# WSN_Gateway_v3.net
KiCad netlist of a schematic drawn in EAGLE
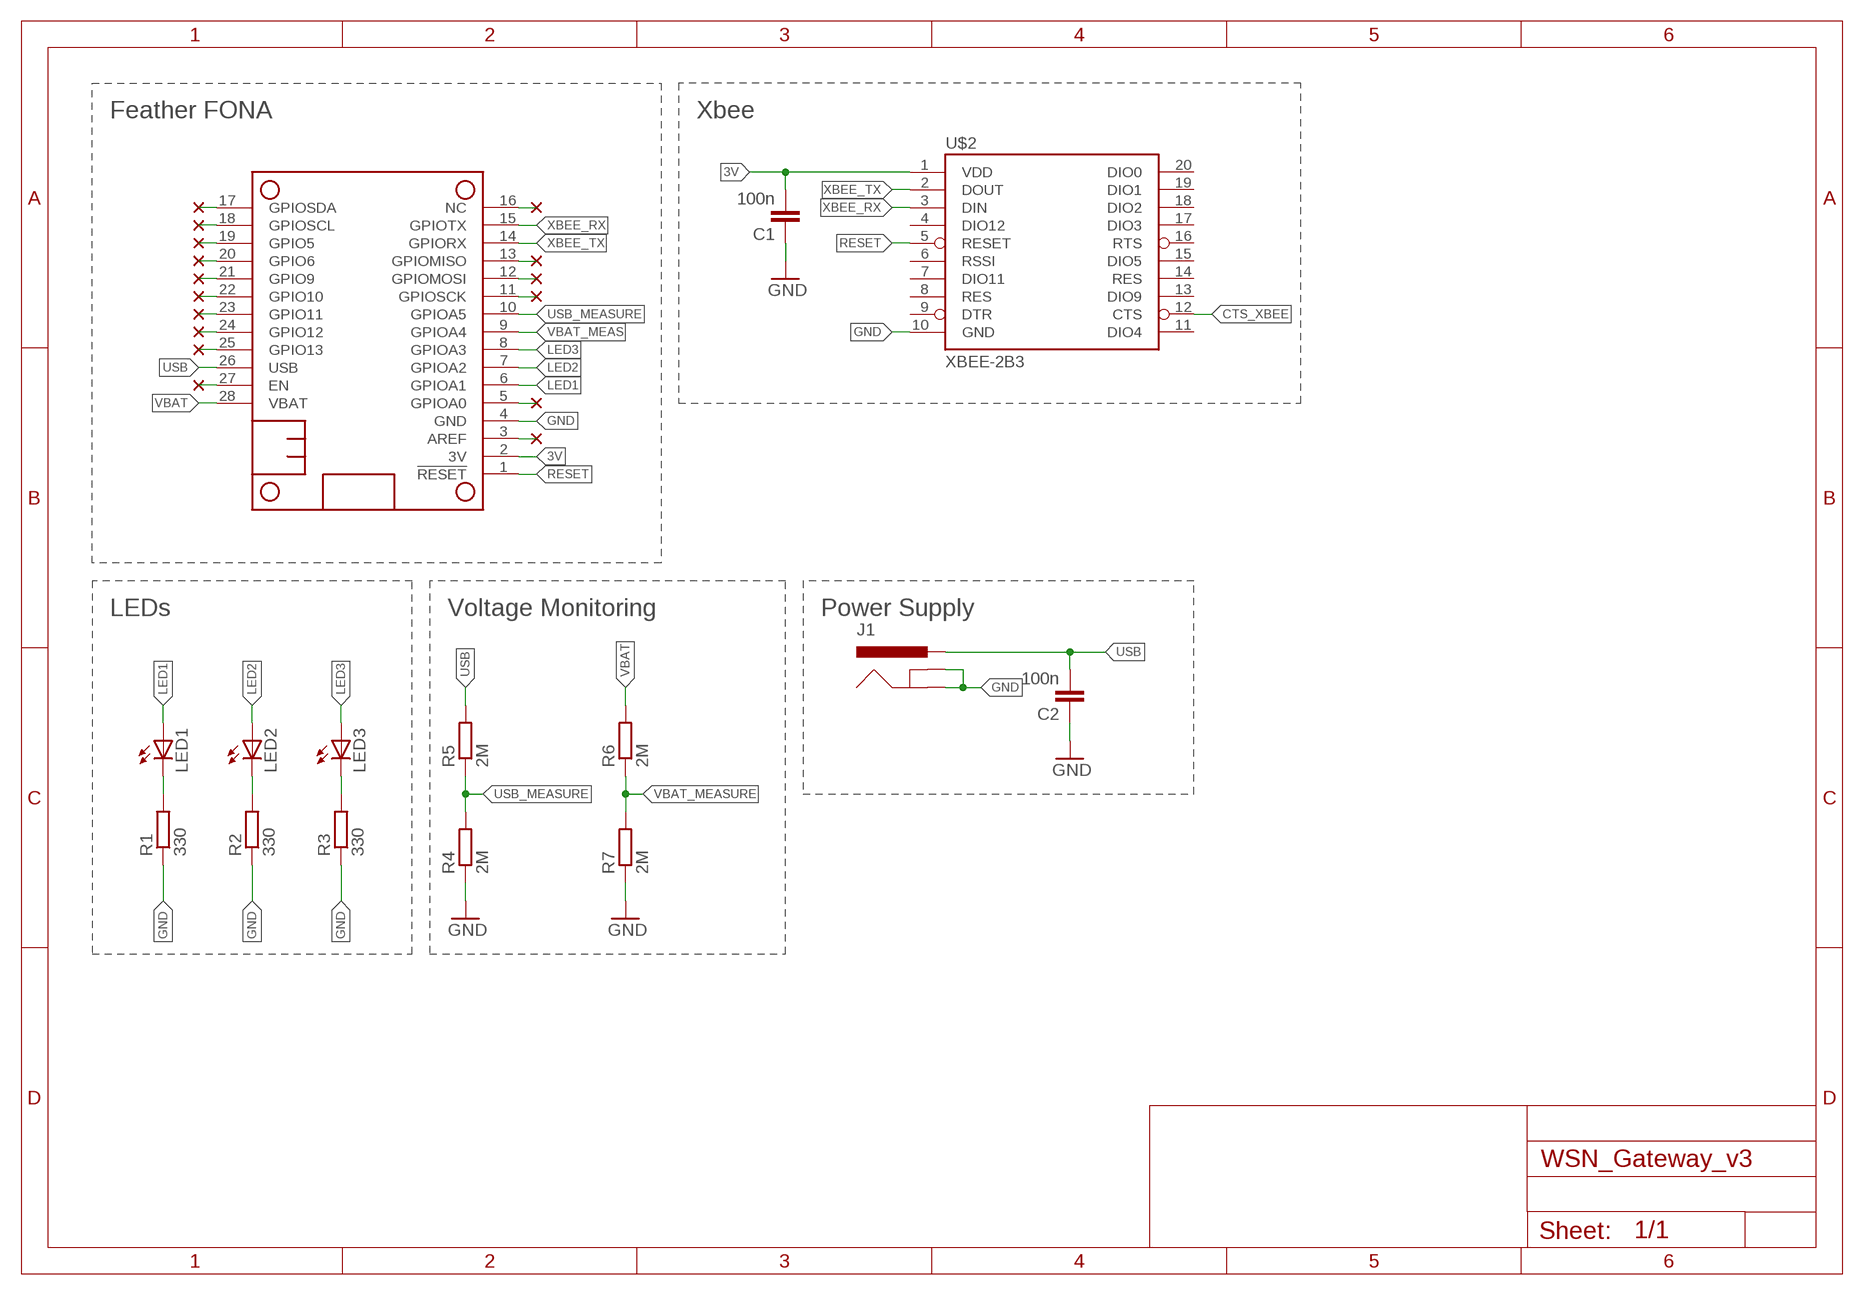
[diagram p0: schematic, sheet 1]

(export (version "E")
  (design (tool "Eeschema 10.0.6"))
  (components
    (comp (ref "C1")
      (value "100n")
      (footprint "eagle-import:C0805")
      (libsource (lib "eagle-import") (part "C"))
    )
    (comp (ref "C2")
      (value "100n")
      (footprint "eagle-import:C0805")
      (libsource (lib "eagle-import") (part "C"))
    )
    (comp (ref "J1")
      (value "5.5x2.1mm Barrel")
      (footprint "eagle-import:POWER_JACK_SMD")
      (libsource (lib "eagle-import") (part "POWER_JACKSMD"))
    )
    (comp (ref "LED1")
      (value "LEDCHIPLED_0805")
      (footprint "eagle-import:CHIPLED_0805")
      (libsource (lib "eagle-import") (part "LEDCHIPLED_0805"))
    )
    (comp (ref "LED2")
      (value "LEDCHIPLED_0805")
      (footprint "eagle-import:CHIPLED_0805")
      (libsource (lib "eagle-import") (part "LEDCHIPLED_0805"))
    )
    (comp (ref "LED3")
      (value "LEDCHIPLED_0805")
      (footprint "eagle-import:CHIPLED_0805")
      (libsource (lib "eagle-import") (part "LEDCHIPLED_0805"))
    )
    (comp (ref "MS1")
      (value "FEATHERWING_NODIM_NOHOLES")
      (footprint "eagle-import:FEATHERWING_DIM_2")
      (libsource (lib "eagle-import") (part "FEATHERWING_NODIM_NOHOLES"))
    )
    (comp (ref "R1")
      (value "330")
      (footprint "eagle-import:R0805")
      (libsource (lib "eagle-import") (part "R-EU_R0805"))
    )
    (comp (ref "R2")
      (value "330")
      (footprint "eagle-import:R0805")
      (libsource (lib "eagle-import") (part "R-EU_R0805"))
    )
    (comp (ref "R3")
      (value "330")
      (footprint "eagle-import:R0805")
      (libsource (lib "eagle-import") (part "R-EU_R0805"))
    )
    (comp (ref "R4")
      (value "2M")
      (footprint "eagle-import:R0805")
      (libsource (lib "eagle-import") (part "R-EU_R0805"))
    )
    (comp (ref "R5")
      (value "2M")
      (footprint "eagle-import:R0805")
      (libsource (lib "eagle-import") (part "R-EU_R0805"))
    )
    (comp (ref "R6")
      (value "2M")
      (footprint "eagle-import:R0805")
      (libsource (lib "eagle-import") (part "R-EU_R0805"))
    )
    (comp (ref "R7")
      (value "2M")
      (footprint "eagle-import:R0805")
      (libsource (lib "eagle-import") (part "R-EU_R0805"))
    )
    (comp (ref "U$2")
      (value "XBEE-2B3")
      (footprint "eagle-import:XBEE-SMD")
      (libsource (lib "eagle-import") (part "XBEE-2B3"))
    )
  )
  (nets
    (net (code "1") (name "3V") (class "Default")
      (node (ref "C1") (pin "2") (pinfunction "2_2") (pintype "passive"))
      (node (ref "MS1") (pin "2") (pinfunction "3V_2") (pintype "power_in"))
      (node (ref "U$2") (pin "1") (pinfunction "VDD_1") (pintype "power_in"))
    )
    (net (code "2") (name "CTS_XBEE") (class "Default")
      (node (ref "U$2") (pin "12") (pinfunction "CTS_12") (pintype "output"))
    )
    (net (code "3") (name "GND") (class "Default")
      (node (ref "C1") (pin "1") (pinfunction "1_1") (pintype "passive"))
      (node (ref "C2") (pin "1") (pinfunction "1_1") (pintype "passive"))
      (node (ref "J1") (pin "GND") (pinfunction "GNDBREAK_GND") (pintype "bidirectional"))
      (node (ref "J1") (pin "P$4") (pinfunction "GND_P$4") (pintype "bidirectional"))
      (node (ref "MS1") (pin "4") (pinfunction "GND_4") (pintype "power_in"))
      (node (ref "R1") (pin "1") (pinfunction "1_1") (pintype "passive"))
      (node (ref "R2") (pin "1") (pinfunction "1_1") (pintype "passive"))
      (node (ref "R3") (pin "1") (pinfunction "1_1") (pintype "passive"))
      (node (ref "R4") (pin "1") (pinfunction "1_1") (pintype "passive"))
      (node (ref "R7") (pin "1") (pinfunction "1_1") (pintype "passive"))
      (node (ref "U$2") (pin "10") (pinfunction "GND_10") (pintype "power_in"))
    )
    (net (code "4") (name "LED1") (class "Default")
      (node (ref "LED1") (pin "A") (pinfunction "A_A") (pintype "passive"))
      (node (ref "MS1") (pin "6") (pinfunction "GPIOA1_6") (pintype "bidirectional"))
    )
    (net (code "5") (name "LED2") (class "Default")
      (node (ref "LED2") (pin "A") (pinfunction "A_A") (pintype "passive"))
      (node (ref "MS1") (pin "7") (pinfunction "GPIOA2_7") (pintype "bidirectional"))
    )
    (net (code "6") (name "LED3") (class "Default")
      (node (ref "LED3") (pin "A") (pinfunction "A_A") (pintype "passive"))
      (node (ref "MS1") (pin "8") (pinfunction "GPIOA3_8") (pintype "bidirectional"))
    )
    (net (code "7") (name "Net-(LED1-PadC)") (class "Default")
      (node (ref "LED1") (pin "C") (pinfunction "C_C") (pintype "passive"))
      (node (ref "R1") (pin "2") (pinfunction "2_2") (pintype "passive"))
    )
    (net (code "8") (name "Net-(LED2-PadC)") (class "Default")
      (node (ref "LED2") (pin "C") (pinfunction "C_C") (pintype "passive"))
      (node (ref "R2") (pin "2") (pinfunction "2_2") (pintype "passive"))
    )
    (net (code "9") (name "Net-(LED3-PadC)") (class "Default")
      (node (ref "LED3") (pin "C") (pinfunction "C_C") (pintype "passive"))
      (node (ref "R3") (pin "2") (pinfunction "2_2") (pintype "passive"))
    )
    (net (code "10") (name "RESET") (class "Default")
      (node (ref "MS1") (pin "1") (pinfunction "~{RESET}_1") (pintype "input"))
      (node (ref "U$2") (pin "5") (pinfunction "RESET_5") (pintype "input"))
    )
    (net (code "11") (name "USB") (class "Default")
      (node (ref "C2") (pin "2") (pinfunction "2_2") (pintype "passive"))
      (node (ref "J1") (pin "VIN0") (pinfunction "PWR_VIN0") (pintype "bidirectional"))
      (node (ref "J1") (pin "VIN1") (pinfunction "PWR_VIN1") (pintype "bidirectional"))
      (node (ref "MS1") (pin "26") (pinfunction "USB_26") (pintype "power_in"))
      (node (ref "R5") (pin "2") (pinfunction "2_2") (pintype "passive"))
    )
    (net (code "12") (name "USB_MEASURE") (class "Default")
      (node (ref "MS1") (pin "10") (pinfunction "GPIOA5_10") (pintype "bidirectional"))
      (node (ref "R4") (pin "2") (pinfunction "2_2") (pintype "passive"))
      (node (ref "R5") (pin "1") (pinfunction "1_1") (pintype "passive"))
    )
    (net (code "13") (name "VBAT") (class "Default")
      (node (ref "MS1") (pin "28") (pinfunction "VBAT_28") (pintype "power_in"))
      (node (ref "R6") (pin "2") (pinfunction "2_2") (pintype "passive"))
    )
    (net (code "14") (name "VBAT_MEAS") (class "Default")
      (node (ref "MS1") (pin "9") (pinfunction "GPIOA4_9") (pintype "bidirectional"))
    )
    (net (code "15") (name "VBAT_MEASURE") (class "Default")
      (node (ref "R6") (pin "1") (pinfunction "1_1") (pintype "passive"))
      (node (ref "R7") (pin "2") (pinfunction "2_2") (pintype "passive"))
    )
    (net (code "16") (name "XBEE_RX") (class "Default")
      (node (ref "MS1") (pin "15") (pinfunction "GPIOTX_15") (pintype "bidirectional"))
      (node (ref "U$2") (pin "3") (pinfunction "DIN_3") (pintype "input"))
    )
    (net (code "17") (name "XBEE_TX") (class "Default")
      (node (ref "MS1") (pin "14") (pinfunction "GPIORX_14") (pintype "bidirectional"))
      (node (ref "U$2") (pin "2") (pinfunction "DOUT_2") (pintype "output"))
    )
    (net (code "18") (name "unconnected-(MS1-AREF-Pad3)") (class "Default")
      (node (ref "MS1") (pin "3") (pinfunction "AREF_3") (pintype "passive"))
    )
    (net (code "19") (name "unconnected-(MS1-EN-Pad27)") (class "Default")
      (node (ref "MS1") (pin "27") (pinfunction "EN_27") (pintype "passive"))
    )
    (net (code "20") (name "unconnected-(MS1-GPIO5-Pad19)") (class "Default")
      (node (ref "MS1") (pin "19") (pinfunction "GPIO5_19") (pintype "bidirectional"))
    )
    (net (code "21") (name "unconnected-(MS1-GPIO6-Pad20)") (class "Default")
      (node (ref "MS1") (pin "20") (pinfunction "GPIO6_20") (pintype "bidirectional"))
    )
    (net (code "22") (name "unconnected-(MS1-GPIO9-Pad21)") (class "Default")
      (node (ref "MS1") (pin "21") (pinfunction "GPIO9_21") (pintype "bidirectional"))
    )
    (net (code "23") (name "unconnected-(MS1-GPIO10-Pad22)") (class "Default")
      (node (ref "MS1") (pin "22") (pinfunction "GPIO10_22") (pintype "bidirectional"))
    )
    (net (code "24") (name "unconnected-(MS1-GPIO11-Pad23)") (class "Default")
      (node (ref "MS1") (pin "23") (pinfunction "GPIO11_23") (pintype "bidirectional"))
    )
    (net (code "25") (name "unconnected-(MS1-GPIO12-Pad24)") (class "Default")
      (node (ref "MS1") (pin "24") (pinfunction "GPIO12_24") (pintype "bidirectional"))
    )
    (net (code "26") (name "unconnected-(MS1-GPIO13-Pad25)") (class "Default")
      (node (ref "MS1") (pin "25") (pinfunction "GPIO13_25") (pintype "bidirectional"))
    )
    (net (code "27") (name "unconnected-(MS1-GPIOA0-Pad5)") (class "Default")
      (node (ref "MS1") (pin "5") (pinfunction "GPIOA0_5") (pintype "bidirectional"))
    )
    (net (code "28") (name "unconnected-(MS1-GPIOMISO-Pad13)") (class "Default")
      (node (ref "MS1") (pin "13") (pinfunction "GPIOMISO_13") (pintype "bidirectional"))
    )
    (net (code "29") (name "unconnected-(MS1-GPIOMOSI-Pad12)") (class "Default")
      (node (ref "MS1") (pin "12") (pinfunction "GPIOMOSI_12") (pintype "bidirectional"))
    )
    (net (code "30") (name "unconnected-(MS1-GPIOSCK-Pad11)") (class "Default")
      (node (ref "MS1") (pin "11") (pinfunction "GPIOSCK_11") (pintype "bidirectional"))
    )
    (net (code "31") (name "unconnected-(MS1-GPIOSCL-Pad18)") (class "Default")
      (node (ref "MS1") (pin "18") (pinfunction "GPIOSCL_18") (pintype "bidirectional"))
    )
    (net (code "32") (name "unconnected-(MS1-GPIOSDA-Pad17)") (class "Default")
      (node (ref "MS1") (pin "17") (pinfunction "GPIOSDA_17") (pintype "bidirectional"))
    )
    (net (code "33") (name "unconnected-(MS1-NC-Pad16)") (class "Default")
      (node (ref "MS1") (pin "16") (pinfunction "NC_16") (pintype "passive"))
    )
    (net (code "34") (name "unconnected-(U$2-DIO0-Pad20)") (class "Default")
      (node (ref "U$2") (pin "20") (pinfunction "DIO0_20") (pintype "bidirectional"))
    )
    (net (code "35") (name "unconnected-(U$2-DIO1-Pad19)") (class "Default")
      (node (ref "U$2") (pin "19") (pinfunction "DIO1_19") (pintype "bidirectional"))
    )
    (net (code "36") (name "unconnected-(U$2-DIO2-Pad18)") (class "Default")
      (node (ref "U$2") (pin "18") (pinfunction "DIO2_18") (pintype "bidirectional"))
    )
    (net (code "37") (name "unconnected-(U$2-DIO3-Pad17)") (class "Default")
      (node (ref "U$2") (pin "17") (pinfunction "DIO3_17") (pintype "bidirectional"))
    )
    (net (code "38") (name "unconnected-(U$2-DIO4-Pad11)") (class "Default")
      (node (ref "U$2") (pin "11") (pinfunction "DIO4_11") (pintype "bidirectional"))
    )
    (net (code "39") (name "unconnected-(U$2-DIO5-Pad15)") (class "Default")
      (node (ref "U$2") (pin "15") (pinfunction "DIO5_15") (pintype "bidirectional"))
    )
    (net (code "40") (name "unconnected-(U$2-DIO9-Pad13)") (class "Default")
      (node (ref "U$2") (pin "13") (pinfunction "DIO9_13") (pintype "bidirectional"))
    )
    (net (code "41") (name "unconnected-(U$2-DIO11-Pad7)") (class "Default")
      (node (ref "U$2") (pin "7") (pinfunction "DIO11_7") (pintype "bidirectional"))
    )
    (net (code "42") (name "unconnected-(U$2-DIO12-Pad4)") (class "Default")
      (node (ref "U$2") (pin "4") (pinfunction "DIO12_4") (pintype "bidirectional"))
    )
    (net (code "43") (name "unconnected-(U$2-DTR-Pad9)") (class "Default")
      (node (ref "U$2") (pin "9") (pinfunction "DTR_9") (pintype "bidirectional"))
    )
    (net (code "44") (name "unconnected-(U$2-RES-Pad8)") (class "Default")
      (node (ref "U$2") (pin "8") (pinfunction "RES_8") (pintype "bidirectional"))
    )
    (net (code "45") (name "unconnected-(U$2-RES-Pad14)") (class "Default")
      (node (ref "U$2") (pin "14") (pinfunction "RES_14") (pintype "bidirectional"))
    )
    (net (code "46") (name "unconnected-(U$2-RSSI-Pad6)") (class "Default")
      (node (ref "U$2") (pin "6") (pinfunction "RSSI_6") (pintype "bidirectional"))
    )
    (net (code "47") (name "unconnected-(U$2-RTS-Pad16)") (class "Default")
      (node (ref "U$2") (pin "16") (pinfunction "RTS_16") (pintype "input"))
    )
  )
)
